# Accelerometer.net
KiCad netlist of a schematic drawn in Altium Designer
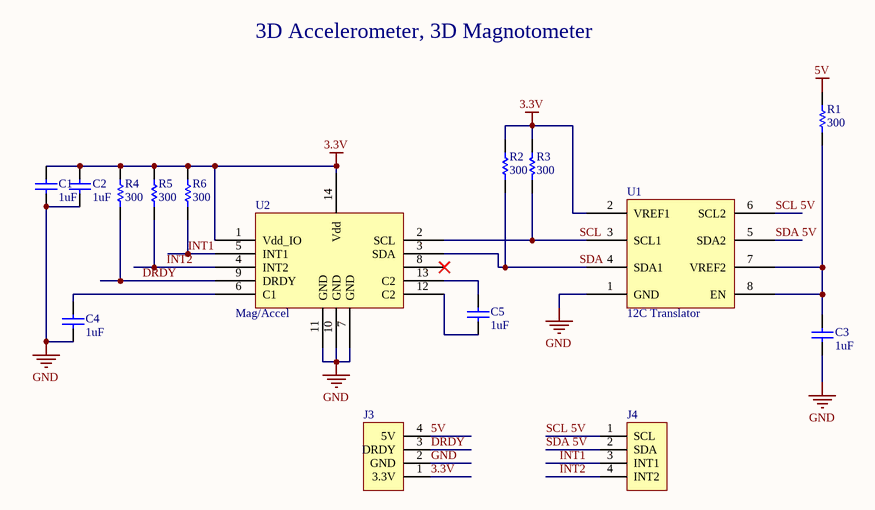
[diagram p0: Accelerometer.SchDoc]

(export (version "E")
  (design (tool "Eeschema 10.0.6"))
  (components
    (comp (ref "C1")
      (value "1uF")
      (footprint "FTPNT_CAPS")
      (description "CAP CER 1UF 25V 10% X7R 1206")
      (fields (field (name "Comment") "Cap") (field (name "PUBLISHER") "Altium Limited"))
      (libsource (lib "Sensors_SchematicLib") (part "Cap"))
    )
    (comp (ref "C2")
      (value "1uF")
      (footprint "FTPNT_CAPS")
      (description "CAP CER 1UF 25V 10% X7R 1206")
      (fields (field (name "Comment") "Cap") (field (name "PUBLISHER") "Altium Limited"))
      (libsource (lib "Sensors_SchematicLib") (part "Cap"))
    )
    (comp (ref "C3")
      (value "1uF")
      (footprint "FTPNT_CAPS")
      (description "CAP CER 1UF 25V 10% X7R 1206")
      (fields (field (name "Comment") "Cap") (field (name "PUBLISHER") "Altium Limited"))
      (libsource (lib "Sensors_SchematicLib") (part "Cap"))
    )
    (comp (ref "C4")
      (value "1uF")
      (footprint "FTPNT_CAPS")
      (description "CAP CER 1UF 25V 10% X7R 1206")
      (fields (field (name "Comment") "Cap") (field (name "PUBLISHER") "Altium Limited"))
      (libsource (lib "Sensors_SchematicLib") (part "Cap"))
    )
    (comp (ref "C5")
      (value "1uF")
      (footprint "FTPNT_CAPS")
      (description "CAP CER 1UF 25V 10% X7R 1206")
      (fields (field (name "Comment") "Cap") (field (name "PUBLISHER") "Altium Limited"))
      (libsource (lib "Sensors_SchematicLib") (part "Cap"))
    )
    (comp (ref "J3")
      (value "Header 4")
      (footprint "HDR1X4")
      (description "CONN HEADER 4POS .100 STR TIN")
      (fields (field (name "PUBLISHER") "Altium Limited"))
      (libsource (lib "Miscellaneous Connectors") (part "Header 4"))
    )
    (comp (ref "J4")
      (value "Header 4")
      (footprint "HDR1X4")
      (description "CONN HEADER 4POS .100 STR TIN")
      (fields (field (name "PUBLISHER") "Altium Limited"))
      (libsource (lib "") (part "Header 4_1"))
    )
    (comp (ref "R1")
      (value "300")
      (footprint "FTPNT_RESISTORS")
      (description "RES 300 OHM 1/4W 1% 1206 SMD")
      (fields (field (name "Comment") "Res1") (field (name "PUBLISHER") "Altium Limited"))
      (libsource (lib "Sensors_SchematicLib") (part "Res1"))
    )
    (comp (ref "R2")
      (value "300")
      (footprint "FTPNT_RESISTORS")
      (description "RES 300 OHM 1/4W 1% 1206 SMD")
      (fields (field (name "Comment") "Res1") (field (name "PUBLISHER") "Altium Limited"))
      (libsource (lib "Sensors_SchematicLib") (part "Res1"))
    )
    (comp (ref "R3")
      (value "300")
      (footprint "FTPNT_RESISTORS")
      (description "RES 300 OHM 1/4W 1% 1206 SMD")
      (fields (field (name "Comment") "Res1") (field (name "PUBLISHER") "Altium Limited"))
      (libsource (lib "Sensors_SchematicLib") (part "Res1"))
    )
    (comp (ref "R4")
      (value "300")
      (footprint "FTPNT_RESISTORS")
      (description "RES 300 OHM 1/4W 1% 1206 SMD")
      (fields (field (name "Comment") "Res1") (field (name "PUBLISHER") "Altium Limited"))
      (libsource (lib "Sensors_SchematicLib") (part "Res1"))
    )
    (comp (ref "R5")
      (value "300")
      (footprint "FTPNT_RESISTORS")
      (description "RES 300 OHM 1/4W 1% 1206 SMD")
      (fields (field (name "Comment") "Res1") (field (name "PUBLISHER") "Altium Limited"))
      (libsource (lib "Sensors_SchematicLib") (part "Res1"))
    )
    (comp (ref "R6")
      (value "300")
      (footprint "FTPNT_RESISTORS")
      (description "RES 300 OHM 1/4W 1% 1206 SMD")
      (fields (field (name "Comment") "Res1") (field (name "PUBLISHER") "Altium Limited"))
      (libsource (lib "Sensors_SchematicLib") (part "Res1"))
    )
    (comp (ref "U1")
      (value "12C Translator")
      (footprint "FTPNT_I2CTRANSLATOR")
      (description "IC LEVEL TRANSLATOR 8-SOIC")
      (libsource (lib "Sensors_Schem") (part "Translator"))
    )
    (comp (ref "U2")
      (value "Mag/Accel")
      (footprint "FTPNT_MAG/ACC")
      (description "ACCELEROMETER/MAGNETOMETER LGA14")
      (libsource (lib "Sensors_Schem") (part "Mag/Accel Header"))
    )
  )
  (nets
    (net (code "1") (name "/DRDY") (class "Default")
      (node (ref "J3") (pin "3") (pinfunction "DRDY_3") (pintype "passive"))
      (node (ref "R4") (pin "1") (pinfunction "1_1") (pintype "passive"))
      (node (ref "U2") (pin "9") (pinfunction "DRDY_9") (pintype "passive"))
    )
    (net (code "2") (name "/INT1") (class "Default")
      (node (ref "J4") (pin "3") (pinfunction "INT1_3") (pintype "passive"))
      (node (ref "R6") (pin "1") (pinfunction "1_1") (pintype "passive"))
      (node (ref "U2") (pin "5") (pinfunction "INT1_5") (pintype "passive"))
    )
    (net (code "3") (name "/INT2") (class "Default")
      (node (ref "J4") (pin "4") (pinfunction "INT2_4") (pintype "passive"))
      (node (ref "R5") (pin "1") (pinfunction "1_1") (pintype "passive"))
      (node (ref "U2") (pin "4") (pinfunction "INT2_4") (pintype "passive"))
    )
    (net (code "4") (name "/SCL") (class "Default")
      (node (ref "R3") (pin "1") (pinfunction "1_1") (pintype "passive"))
      (node (ref "U1") (pin "3") (pinfunction "SCL1_3") (pintype "passive"))
      (node (ref "U2") (pin "2") (pinfunction "SCL_2") (pintype "passive"))
    )
    (net (code "5") (name "/SCL 5V") (class "Default")
      (node (ref "J4") (pin "1") (pinfunction "SCL_1") (pintype "passive"))
      (node (ref "U1") (pin "6") (pinfunction "SCL2_6") (pintype "passive"))
    )
    (net (code "6") (name "/SDA") (class "Default")
      (node (ref "R2") (pin "1") (pinfunction "1_1") (pintype "passive"))
      (node (ref "U1") (pin "4") (pinfunction "SDA1_4") (pintype "passive"))
      (node (ref "U2") (pin "3") (pinfunction "SDA_3") (pintype "passive"))
    )
    (net (code "7") (name "/SDA 5V") (class "Default")
      (node (ref "J4") (pin "2") (pinfunction "SDA_2") (pintype "passive"))
      (node (ref "U1") (pin "5") (pinfunction "SDA2_5") (pintype "passive"))
    )
    (net (code "8") (name "3.3V") (class "Default")
      (node (ref "C1") (pin "2") (pinfunction "2_2") (pintype "passive"))
      (node (ref "C2") (pin "2") (pinfunction "2_2") (pintype "passive"))
      (node (ref "J3") (pin "1") (pinfunction "3.3V_1") (pintype "passive"))
      (node (ref "R2") (pin "2") (pinfunction "2_2") (pintype "passive"))
      (node (ref "R3") (pin "2") (pinfunction "2_2") (pintype "passive"))
      (node (ref "R4") (pin "2") (pinfunction "2_2") (pintype "passive"))
      (node (ref "R5") (pin "2") (pinfunction "2_2") (pintype "passive"))
      (node (ref "R6") (pin "2") (pinfunction "2_2") (pintype "passive"))
      (node (ref "U1") (pin "2") (pinfunction "VREF1_2") (pintype "passive"))
      (node (ref "U2") (pin "1") (pinfunction "Vdd_IO_1") (pintype "passive"))
      (node (ref "U2") (pin "14") (pinfunction "Vdd_14") (pintype "passive"))
    )
    (net (code "9") (name "5V") (class "Default")
      (node (ref "J3") (pin "4") (pinfunction "5V_4") (pintype "passive"))
      (node (ref "R1") (pin "2") (pinfunction "2_2") (pintype "passive"))
    )
    (net (code "10") (name "GND") (class "Default")
      (node (ref "C1") (pin "1") (pinfunction "1_1") (pintype "passive"))
      (node (ref "C2") (pin "1") (pinfunction "1_1") (pintype "passive"))
      (node (ref "C3") (pin "1") (pinfunction "1_1") (pintype "passive"))
      (node (ref "C4") (pin "1") (pinfunction "1_1") (pintype "passive"))
      (node (ref "J3") (pin "2") (pinfunction "GND_2") (pintype "passive"))
      (node (ref "U1") (pin "1") (pinfunction "GND_1") (pintype "passive"))
      (node (ref "U2") (pin "10") (pinfunction "GND_10") (pintype "passive"))
      (node (ref "U2") (pin "11") (pinfunction "GND_11") (pintype "passive"))
      (node (ref "U2") (pin "7") (pinfunction "GND_7") (pintype "passive"))
    )
    (net (code "11") (name "Net-(C5-Pad1)") (class "Default")
      (node (ref "C5") (pin "1") (pinfunction "1_1") (pintype "passive"))
      (node (ref "U2") (pin "12") (pinfunction "C2_12") (pintype "passive"))
    )
    (net (code "12") (name "Net-(C5-Pad2)") (class "Default")
      (node (ref "C5") (pin "2") (pinfunction "2_2") (pintype "passive"))
      (node (ref "U2") (pin "13") (pinfunction "C2_13") (pintype "passive"))
    )
    (net (code "13") (name "Net-(U1-EN)") (class "Default")
      (node (ref "C3") (pin "2") (pinfunction "2_2") (pintype "passive"))
      (node (ref "R1") (pin "1") (pinfunction "1_1") (pintype "passive"))
      (node (ref "U1") (pin "7") (pinfunction "VREF2_7") (pintype "passive"))
      (node (ref "U1") (pin "8") (pinfunction "EN_8") (pintype "passive"))
    )
    (net (code "14") (name "Net-(U2-C1)") (class "Default")
      (node (ref "C4") (pin "2") (pinfunction "2_2") (pintype "passive"))
      (node (ref "U2") (pin "6") (pinfunction "C1_6") (pintype "passive"))
    )
    (net (code "15") (name "unconnected-(U2-Pad8)") (class "Default")
      (node (ref "U2") (pin "8") (pintype "passive+no_connect"))
    )
  )
)
